# SPI.net
KiCad netlist of a schematic drawn in Altium Designer
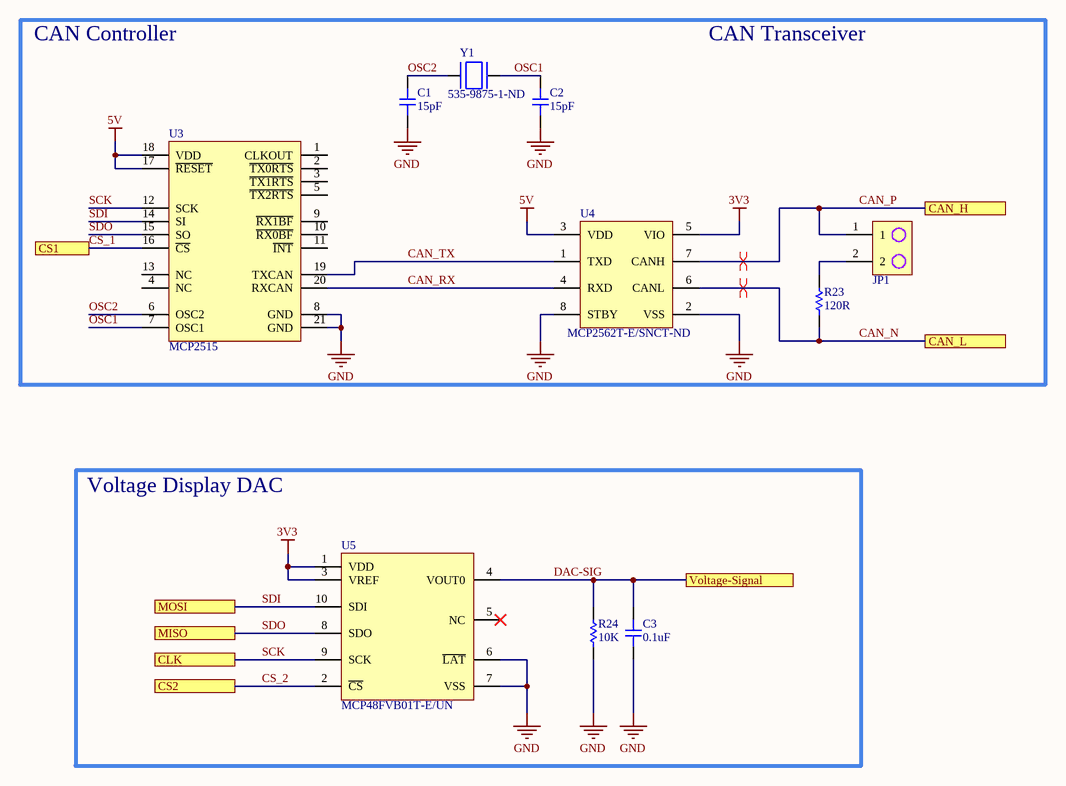
[diagram p0: SPI.SchDoc]

(export (version "E")
  (design (tool "Eeschema 10.0.6"))
  (components
    (comp (ref "C1")
      (value "15pF")
      (footprint "CAP-0603")
      (description "CAP CER 15PF 100V C0G/NP0 0603")
      (fields
        (field (name "MANUFACTURER") "Murata")
        (field (name "MANUFACTURER PART NUMBER") "GRM1885C2A150JA01D")
      )
      (libsource (lib "Capacitors") (part "0603-15pF-100V"))
    )
    (comp (ref "C2")
      (value "15pF")
      (footprint "CAP-0603")
      (description "CAP CER 15PF 100V C0G/NP0 0603")
      (fields
        (field (name "MANUFACTURER") "Murata")
        (field (name "MANUFACTURER PART NUMBER") "GRM1885C2A150JA01D")
      )
      (libsource (lib "Capacitors") (part "0603-15pF-100V"))
    )
    (comp (ref "C3")
      (value "0.1uF")
      (footprint "CAP-0805")
      (description "CAP CER 0.1UF 50V Y5V 0805")
      (fields
        (field (name "MANUFACTURER") "KEMET")
        (field (name "MANUFACTURER PART NUMBER") "C0805C104Z5VACTU")
      )
      (libsource (lib "WorkshopSlib") (part "C0805C104Z5VACTU"))
    )
    (comp (ref "JP1")
      (value "732-5315-ND")
      (footprint "2PIN-JP")
      (description "CONN HEADER VERT 2POS 2.54MM")
      (libsource (lib "Connectors") (part "2PIN-TEST"))
    )
    (comp (ref "R23")
      (value "120R")
      (footprint "RES-0603")
      (description "RES SMD 120 OHM 1% 1/10W 0603")
      (fields
        (field (name "MANUFACTURER") "Yageo")
        (field (name "MANUFACTURER PART NUMBER") "RC0603FR-07120RL")
      )
      (libsource (lib "Resistors") (part "0603-120R"))
    )
    (comp (ref "R24")
      (value "10K")
      (footprint "RES-0603")
      (description "RES SMD 10K OHM 5% 1/10W 0603")
      (fields
        (field (name "MANUFACTURER") "Yageo")
        (field (name "MANUFACTURER PART NUMBER") "RC0603JR-0710KL")
      )
      (libsource (lib "WorkshopSlib") (part "RC0603JR-0710KL"))
    )
    (comp (ref "U3")
      (value "MCP2515")
      (footprint "QFN20-EP")
      (fields
        (field (name "MANUFACTURER") "Microchip")
        (field (name "MANUFACTURER PART NUMBER") "MCP2515-E/ML")
      )
      (libsource (lib "WorkshopSlib") (part "MCP2515-E/ML"))
    )
    (comp (ref "U4")
      (value "MCP2562T-E/SNCT-ND")
      (footprint "8-SOIC w/o THRM")
      (description "IC TRANSCEIVER HALF 1/1 8SOIC")
      (fields
        (field (name "MANUFACTURER") "Microchip")
        (field (name "MANUFACTURER PART NUMBER") "MCP2562T-E/SN")
      )
      (libsource (lib "ICs") (part "CAN TRAN-MCP2562T-E/SN"))
    )
    (comp (ref "U5")
      (value "MCP48FVB01T-E/UN")
      (footprint "10MSOP")
      (description "IC DAC 8BIT V-OUT 10MSOP")
      (fields (field (name "MANUFACTURER") "Microchip"))
      (libsource (lib "WorkshopSlib") (part "MCP48FVB01T-E/UN"))
    )
    (comp (ref "Y1")
      (value "535-9875-1-ND")
      (footprint "CRYSTAL-ABLS2")
      (description "CRYSTAL 16.0000MHZ 18PF SMD")
      (fields
        (field (name "MANUFACTURER") "Abracon")
        (field (name "MANUFACTURER PART NUMBER") "ABLS2-16.000MHZ-D4Y-T")
      )
      (libsource (lib "Misc") (part "Crysatl-16Mhz"))
    )
  )
  (nets
    (net (code "1") (name "/CAN_N") (class "Default")
      (node (ref "R23") (pin "1") (pinfunction "1_1") (pintype "passive"))
      (node (ref "U4") (pin "6") (pinfunction "CANL_6") (pintype "passive"))
    )
    (net (code "2") (name "/CAN_P") (class "Default")
      (node (ref "JP1") (pin "1") (pinfunction "1_1") (pintype "passive"))
      (node (ref "U4") (pin "7") (pinfunction "CANH_7") (pintype "passive"))
    )
    (net (code "3") (name "/CAN_RX") (class "Default")
      (node (ref "U3") (pin "20") (pinfunction "RXCAN_20") (pintype "passive"))
      (node (ref "U4") (pin "4") (pinfunction "RXD_4") (pintype "passive"))
    )
    (net (code "4") (name "/CAN_TX") (class "Default")
      (node (ref "U3") (pin "19") (pinfunction "TXCAN_19") (pintype "passive"))
      (node (ref "U4") (pin "1") (pinfunction "TXD_1") (pintype "passive"))
    )
    (net (code "5") (name "/CS_1") (class "Default")
      (node (ref "U3") (pin "16") (pinfunction "~{CS}_16") (pintype "passive"))
    )
    (net (code "6") (name "/CS_2") (class "Default")
      (node (ref "U5") (pin "2") (pinfunction "~{CS}_2") (pintype "passive"))
    )
    (net (code "7") (name "/DAC-SIG") (class "Default")
      (node (ref "C3") (pin "2") (pinfunction "2_2") (pintype "passive"))
      (node (ref "R24") (pin "2") (pinfunction "2_2") (pintype "passive"))
      (node (ref "U5") (pin "4") (pinfunction "VOUT0_4") (pintype "passive"))
    )
    (net (code "8") (name "/OSC1") (class "Default")
      (node (ref "C2") (pin "2") (pinfunction "2_2") (pintype "passive"))
      (node (ref "U3") (pin "7") (pinfunction "OSC1_7") (pintype "passive"))
      (node (ref "Y1") (pin "2") (pinfunction "2_2") (pintype "passive"))
    )
    (net (code "9") (name "/OSC2") (class "Default")
      (node (ref "C1") (pin "2") (pinfunction "2_2") (pintype "passive"))
      (node (ref "U3") (pin "6") (pinfunction "OSC2_6") (pintype "passive"))
      (node (ref "Y1") (pin "1") (pinfunction "1_1") (pintype "passive"))
    )
    (net (code "10") (name "/SCK") (class "Default")
      (node (ref "U3") (pin "12") (pinfunction "SCK_12") (pintype "passive"))
      (node (ref "U5") (pin "9") (pinfunction "SCK_9") (pintype "passive"))
    )
    (net (code "11") (name "/SDI") (class "Default")
      (node (ref "U3") (pin "14") (pinfunction "SI_14") (pintype "passive"))
      (node (ref "U5") (pin "10") (pinfunction "SDI_10") (pintype "passive"))
    )
    (net (code "12") (name "/SDO") (class "Default")
      (node (ref "U3") (pin "15") (pinfunction "SO_15") (pintype "passive"))
      (node (ref "U5") (pin "8") (pinfunction "SDO_8") (pintype "passive"))
    )
    (net (code "13") (name "3V3") (class "Default")
      (node (ref "U4") (pin "5") (pinfunction "VIO_5") (pintype "passive"))
      (node (ref "U5") (pin "1") (pinfunction "VDD_1") (pintype "passive"))
      (node (ref "U5") (pin "3") (pinfunction "VREF_3") (pintype "passive"))
    )
    (net (code "14") (name "5V") (class "Default")
      (node (ref "U3") (pin "17") (pinfunction "~{RESET}_17") (pintype "passive"))
      (node (ref "U3") (pin "18") (pinfunction "VDD_18") (pintype "passive"))
      (node (ref "U4") (pin "3") (pinfunction "VDD_3") (pintype "passive"))
    )
    (net (code "15") (name "GND") (class "Default")
      (node (ref "C1") (pin "1") (pinfunction "1_1") (pintype "passive"))
      (node (ref "C2") (pin "1") (pinfunction "1_1") (pintype "passive"))
      (node (ref "C3") (pin "1") (pinfunction "1_1") (pintype "passive"))
      (node (ref "R24") (pin "1") (pinfunction "1_1") (pintype "passive"))
      (node (ref "U3") (pin "21") (pinfunction "GND_21") (pintype "passive"))
      (node (ref "U3") (pin "8") (pinfunction "GND_8") (pintype "passive"))
      (node (ref "U4") (pin "2") (pinfunction "VSS_2") (pintype "passive"))
      (node (ref "U4") (pin "8") (pinfunction "STBY_8") (pintype "passive"))
      (node (ref "U5") (pin "6") (pinfunction "~{LAT}_6") (pintype "passive"))
      (node (ref "U5") (pin "7") (pinfunction "VSS_7") (pintype "passive"))
    )
    (net (code "16") (name "Net-(JP1-Pad2)") (class "Default")
      (node (ref "JP1") (pin "2") (pinfunction "2_2") (pintype "passive"))
      (node (ref "R23") (pin "2") (pinfunction "2_2") (pintype "passive"))
    )
    (net (code "17") (name "unconnected-(U3-CLKOUT-Pad1)") (class "Default")
      (node (ref "U3") (pin "1") (pinfunction "CLKOUT_1") (pintype "passive"))
    )
    (net (code "18") (name "unconnected-(U3-NC-Pad4)") (class "Default")
      (node (ref "U3") (pin "4") (pinfunction "NC_4") (pintype "passive"))
    )
    (net (code "19") (name "unconnected-(U3-NC-Pad13)") (class "Default")
      (node (ref "U3") (pin "13") (pinfunction "NC_13") (pintype "passive"))
    )
    (net (code "20") (name "unconnected-(U3-~{INT}-Pad11)") (class "Default")
      (node (ref "U3") (pin "11") (pinfunction "~{INT}_11") (pintype "passive"))
    )
    (net (code "21") (name "unconnected-(U3-~{RX0BF}-Pad10)") (class "Default")
      (node (ref "U3") (pin "10") (pinfunction "~{RX0BF}_10") (pintype "passive"))
    )
    (net (code "22") (name "unconnected-(U3-~{RX1BF}-Pad9)") (class "Default")
      (node (ref "U3") (pin "9") (pinfunction "~{RX1BF}_9") (pintype "passive"))
    )
    (net (code "23") (name "unconnected-(U3-~{TX0RTS}-Pad2)") (class "Default")
      (node (ref "U3") (pin "2") (pinfunction "~{TX0RTS}_2") (pintype "passive"))
    )
    (net (code "24") (name "unconnected-(U3-~{TX1RTS}-Pad3)") (class "Default")
      (node (ref "U3") (pin "3") (pinfunction "~{TX1RTS}_3") (pintype "passive"))
    )
    (net (code "25") (name "unconnected-(U3-~{TX2RTS}-Pad5)") (class "Default")
      (node (ref "U3") (pin "5") (pinfunction "~{TX2RTS}_5") (pintype "passive"))
    )
    (net (code "26") (name "unconnected-(U5-NC-Pad5)") (class "Default")
      (node (ref "U5") (pin "5") (pinfunction "NC_5") (pintype "passive+no_connect"))
    )
  )
)
